# LDO_3v3_LM2937.net
KiCad netlist of a schematic drawn in Altium Designer
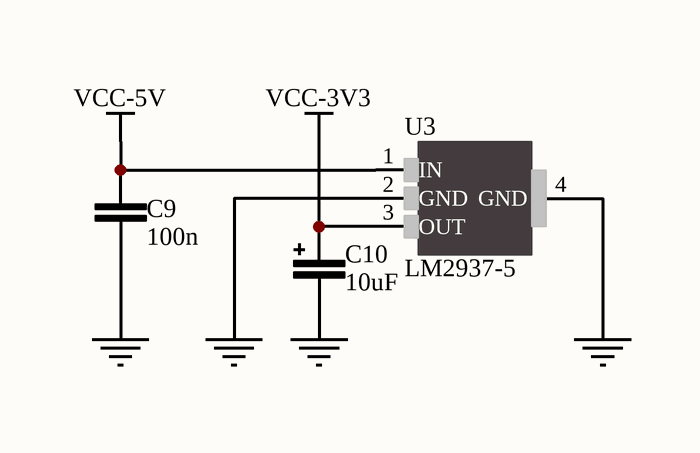
[diagram p0: LDO_3v3_LM2937.SchDoc]

(export (version "E")
  (design (tool "Eeschema 10.0.6"))
  (components
    (comp (ref "C9")
      (value "100n")
      (footprint "CER_0603")
      (description "CAP CER 100n 10V X5R 10% 0603")
      (libsource (lib "Capacitors") (part "06032105"))
    )
    (comp (ref "C10")
      (value "10uF")
      (footprint "TANT_1210")
      (description "CAP TANT 10u")
      (libsource (lib "Capacitors") (part "00001106"))
    )
    (comp (ref "U3")
      (value "LM2937-5")
      (footprint "SOT223")
      (description "IC REG LINEAR 5V 400MA SOT223-4")
      (libsource (lib "Integrated_circuits") (part "00000007"))
    )
  )
  (nets
    (net (code "1") (name "GND") (class "Default")
      (node (ref "C10") (pin "2") (pinfunction "2_2") (pintype "passive"))
      (node (ref "C9") (pin "1") (pinfunction "1_1") (pintype "passive"))
      (node (ref "U3") (pin "2") (pinfunction "GND_2") (pintype "passive"))
      (node (ref "U3") (pin "4") (pinfunction "GND_4") (pintype "passive"))
    )
    (net (code "2") (name "VCC-3V3") (class "Default")
      (node (ref "C10") (pin "1") (pinfunction "1_1") (pintype "passive"))
      (node (ref "U3") (pin "3") (pinfunction "OUT_3") (pintype "passive"))
    )
    (net (code "3") (name "VCC-5V") (class "Default")
      (node (ref "C9") (pin "2") (pinfunction "2_2") (pintype "passive"))
      (node (ref "U3") (pin "1") (pinfunction "IN_1") (pintype "passive"))
    )
  )
)
